# M_Board1_2011.net
KiCad netlist of a schematic drawn in Altium Designer
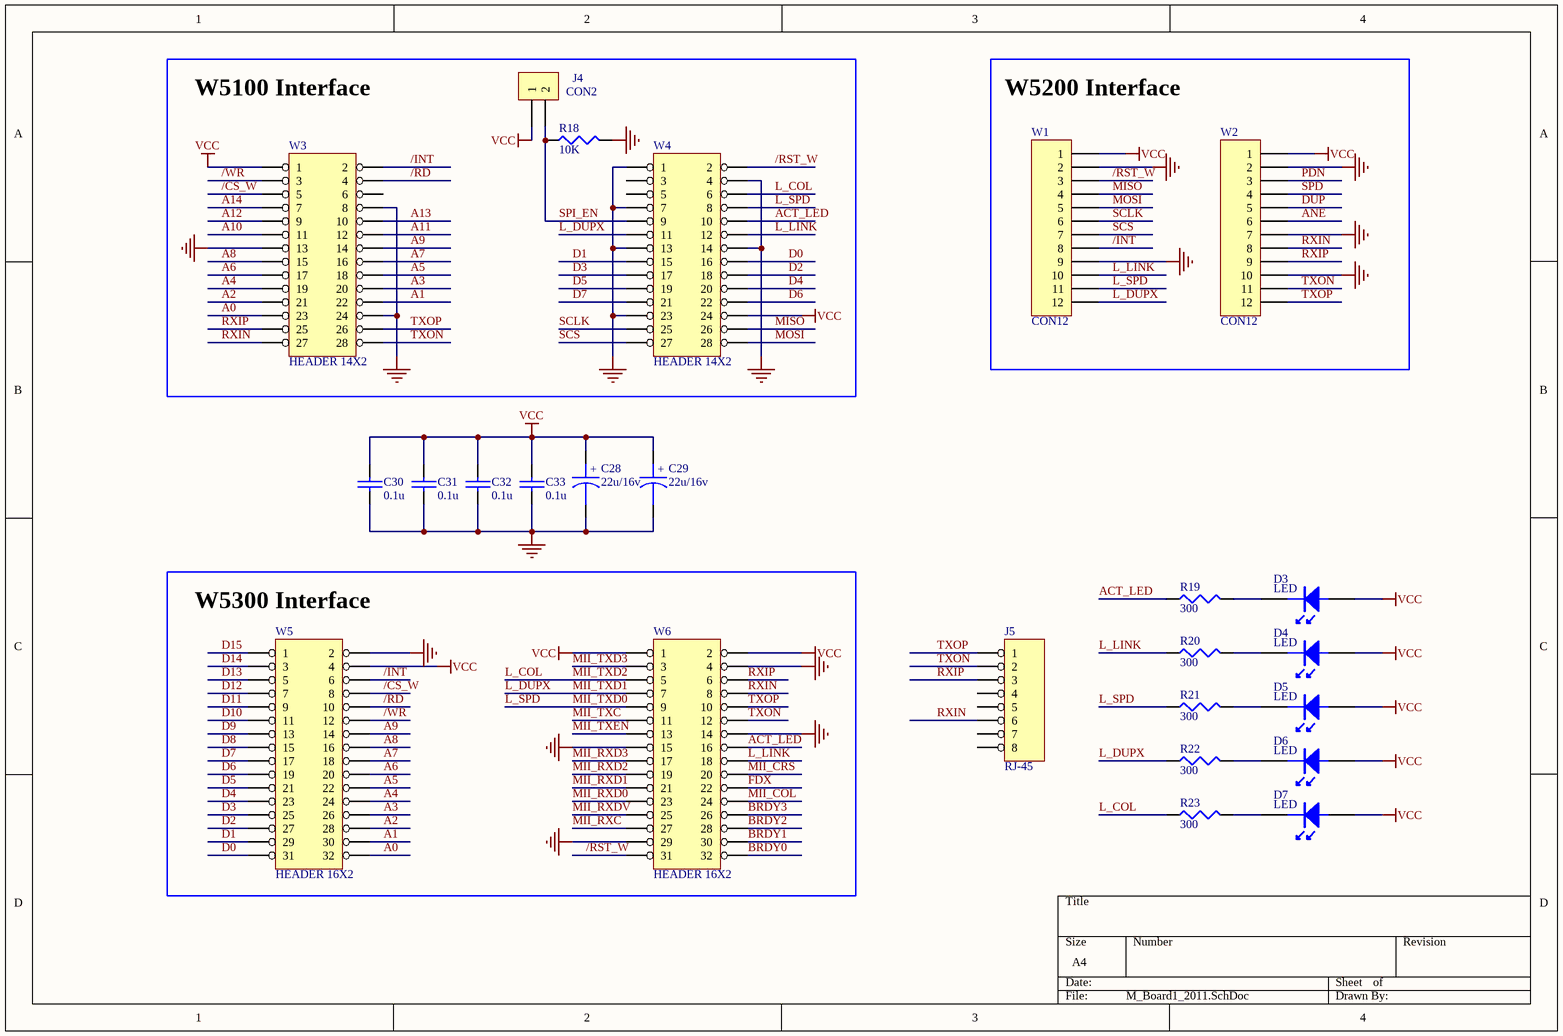
[diagram p0: M_Board1_2011.SchDoc]

(export (version "E")
  (design (tool "Eeschema 10.0.6"))
  (components
    (comp (ref "C28")
      (value "22u/16v")
      (footprint "RB.1/.2N")
      (description "Capacitor")
      (libsource (lib "*") (part "CAPACITOR POL"))
    )
    (comp (ref "C29")
      (value "22u/16v")
      (footprint "RB.1/.2N")
      (description "Capacitor")
      (libsource (lib "*") (part "CAPACITOR POL"))
    )
    (comp (ref "C30")
      (value "0.1u")
      (footprint "0603")
      (description "Capacitor")
      (libsource (lib "*") (part "CAP"))
    )
    (comp (ref "C31")
      (value "0.1u")
      (footprint "0603")
      (description "Capacitor")
      (libsource (lib "*") (part "CAP"))
    )
    (comp (ref "C32")
      (value "0.1u")
      (footprint "0603")
      (description "Capacitor")
      (libsource (lib "*") (part "CAP"))
    )
    (comp (ref "C33")
      (value "0.1u")
      (footprint "0603")
      (description "Capacitor")
      (libsource (lib "*") (part "CAP"))
    )
    (comp (ref "D3") (value "LED") (footprint "LED2P") (libsource (lib "*") (part "LED")))
    (comp (ref "D4") (value "LED") (footprint "LED2P") (libsource (lib "*") (part "LED")))
    (comp (ref "D5") (value "LED") (footprint "LED2P") (libsource (lib "*") (part "LED")))
    (comp (ref "D6") (value "LED") (footprint "LED2P") (libsource (lib "*") (part "LED")))
    (comp (ref "D7") (value "LED") (footprint "LED2P") (libsource (lib "*") (part "LED")))
    (comp (ref "J4")
      (value "CON2")
      (footprint "SIP2")
      (description "Connector")
      (libsource (lib "*") (part "CON2"))
    )
    (comp (ref "J5")
      (value "RJ-45")
      (footprint "RJ45-3")
      (description "8 Pin Header")
      (libsource (lib "*") (part "8 HEADER"))
    )
    (comp (ref "R18") (value "10K") (footprint "0603") (libsource (lib "*") (part "RES1")))
    (comp (ref "R19") (value "300") (footprint "0603") (libsource (lib "*") (part "RES1")))
    (comp (ref "R20") (value "300") (footprint "0603") (libsource (lib "*") (part "RES1")))
    (comp (ref "R21") (value "300") (footprint "0603") (libsource (lib "*") (part "RES1")))
    (comp (ref "R22") (value "300") (footprint "0603") (libsource (lib "*") (part "RES1")))
    (comp (ref "R23") (value "300") (footprint "0603") (libsource (lib "*") (part "RES1")))
    (comp (ref "W1") (value "CON12") (description "Connector") (libsource (lib "*") (part "CON12")))
    (comp (ref "W2") (value "CON12") (description "Connector") (libsource (lib "*") (part "CON12")))
    (comp (ref "W3") (value "HEADER 14X2") (footprint "IDC28-2") (libsource (lib "*") (part "HEADER 14X2")))
    (comp (ref "W4") (value "HEADER 14X2") (footprint "IDC28-2") (libsource (lib "*") (part "HEADER 14X2")))
    (comp (ref "W5") (value "HEADER 16X2") (footprint "IDC32-2") (libsource (lib "*") (part "HEADER 16X2")))
    (comp (ref "W6") (value "HEADER 16X2") (footprint "IDC32-2") (libsource (lib "*") (part "HEADER 16X2")))
  )
  (nets
    (net (code "1") (name "/A0") (class "Default")
      (node (ref "W3") (pin "23") (pinfunction "23_23") (pintype "passive"))
      (node (ref "W5") (pin "32") (pinfunction "32_32") (pintype "passive"))
    )
    (net (code "2") (name "/A1") (class "Default")
      (node (ref "W3") (pin "22") (pinfunction "22_22") (pintype "passive"))
      (node (ref "W5") (pin "30") (pinfunction "30_30") (pintype "passive"))
    )
    (net (code "3") (name "/A2") (class "Default")
      (node (ref "W3") (pin "21") (pinfunction "21_21") (pintype "passive"))
      (node (ref "W5") (pin "28") (pinfunction "28_28") (pintype "passive"))
    )
    (net (code "4") (name "/A3") (class "Default")
      (node (ref "W3") (pin "20") (pinfunction "20_20") (pintype "passive"))
      (node (ref "W5") (pin "26") (pinfunction "26_26") (pintype "passive"))
    )
    (net (code "5") (name "/A4") (class "Default")
      (node (ref "W3") (pin "19") (pinfunction "19_19") (pintype "passive"))
      (node (ref "W5") (pin "24") (pinfunction "24_24") (pintype "passive"))
    )
    (net (code "6") (name "/A5") (class "Default")
      (node (ref "W3") (pin "18") (pinfunction "18_18") (pintype "passive"))
      (node (ref "W5") (pin "22") (pinfunction "22_22") (pintype "passive"))
    )
    (net (code "7") (name "/A6") (class "Default")
      (node (ref "W3") (pin "17") (pinfunction "17_17") (pintype "passive"))
      (node (ref "W5") (pin "20") (pinfunction "20_20") (pintype "passive"))
    )
    (net (code "8") (name "/A7") (class "Default")
      (node (ref "W3") (pin "16") (pinfunction "16_16") (pintype "passive"))
      (node (ref "W5") (pin "18") (pinfunction "18_18") (pintype "passive"))
    )
    (net (code "9") (name "/A8") (class "Default")
      (node (ref "W3") (pin "15") (pinfunction "15_15") (pintype "passive"))
      (node (ref "W5") (pin "16") (pinfunction "16_16") (pintype "passive"))
    )
    (net (code "10") (name "/A9") (class "Default")
      (node (ref "W3") (pin "14") (pinfunction "14_14") (pintype "passive"))
      (node (ref "W5") (pin "14") (pinfunction "14_14") (pintype "passive"))
    )
    (net (code "11") (name "/A10") (class "Default")
      (node (ref "W3") (pin "11") (pinfunction "11_11") (pintype "passive"))
    )
    (net (code "12") (name "/A11") (class "Default")
      (node (ref "W3") (pin "12") (pinfunction "12_12") (pintype "passive"))
    )
    (net (code "13") (name "/A12") (class "Default")
      (node (ref "W3") (pin "9") (pinfunction "9_9") (pintype "passive"))
    )
    (net (code "14") (name "/A13") (class "Default")
      (node (ref "W3") (pin "10") (pinfunction "10_10") (pintype "passive"))
    )
    (net (code "15") (name "/A14") (class "Default")
      (node (ref "W3") (pin "7") (pinfunction "7_7") (pintype "passive"))
    )
    (net (code "16") (name "/ACT_LED") (class "Default")
      (node (ref "R19") (pin "1") (pinfunction "1_1") (pintype "passive"))
      (node (ref "W4") (pin "10") (pinfunction "10_10") (pintype "passive"))
      (node (ref "W6") (pin "16") (pinfunction "16_16") (pintype "passive"))
    )
    (net (code "17") (name "/ANE") (class "Default")
      (node (ref "W2") (pin "6") (pinfunction "6_6") (pintype "passive"))
    )
    (net (code "18") (name "/BRDY0") (class "Default")
      (node (ref "W6") (pin "32") (pinfunction "32_32") (pintype "passive"))
    )
    (net (code "19") (name "/BRDY1") (class "Default")
      (node (ref "W6") (pin "30") (pinfunction "30_30") (pintype "passive"))
    )
    (net (code "20") (name "/BRDY2") (class "Default")
      (node (ref "W6") (pin "28") (pinfunction "28_28") (pintype "passive"))
    )
    (net (code "21") (name "/BRDY3") (class "Default")
      (node (ref "W6") (pin "26") (pinfunction "26_26") (pintype "passive"))
    )
    (net (code "22") (name "/D0") (class "Default")
      (node (ref "W4") (pin "16") (pinfunction "16_16") (pintype "passive"))
      (node (ref "W5") (pin "31") (pinfunction "31_31") (pintype "passive"))
    )
    (net (code "23") (name "/D1") (class "Default")
      (node (ref "W4") (pin "15") (pinfunction "15_15") (pintype "passive"))
      (node (ref "W5") (pin "29") (pinfunction "29_29") (pintype "passive"))
    )
    (net (code "24") (name "/D2") (class "Default")
      (node (ref "W4") (pin "18") (pinfunction "18_18") (pintype "passive"))
      (node (ref "W5") (pin "27") (pinfunction "27_27") (pintype "passive"))
    )
    (net (code "25") (name "/D3") (class "Default")
      (node (ref "W4") (pin "17") (pinfunction "17_17") (pintype "passive"))
      (node (ref "W5") (pin "25") (pinfunction "25_25") (pintype "passive"))
    )
    (net (code "26") (name "/D4") (class "Default")
      (node (ref "W4") (pin "20") (pinfunction "20_20") (pintype "passive"))
      (node (ref "W5") (pin "23") (pinfunction "23_23") (pintype "passive"))
    )
    (net (code "27") (name "/D5") (class "Default")
      (node (ref "W4") (pin "19") (pinfunction "19_19") (pintype "passive"))
      (node (ref "W5") (pin "21") (pinfunction "21_21") (pintype "passive"))
    )
    (net (code "28") (name "/D6") (class "Default")
      (node (ref "W4") (pin "22") (pinfunction "22_22") (pintype "passive"))
      (node (ref "W5") (pin "19") (pinfunction "19_19") (pintype "passive"))
    )
    (net (code "29") (name "/D7") (class "Default")
      (node (ref "W4") (pin "21") (pinfunction "21_21") (pintype "passive"))
      (node (ref "W5") (pin "17") (pinfunction "17_17") (pintype "passive"))
    )
    (net (code "30") (name "/D8") (class "Default")
      (node (ref "W5") (pin "15") (pinfunction "15_15") (pintype "passive"))
    )
    (net (code "31") (name "/D9") (class "Default")
      (node (ref "W5") (pin "13") (pinfunction "13_13") (pintype "passive"))
    )
    (net (code "32") (name "/D10") (class "Default")
      (node (ref "W5") (pin "11") (pinfunction "11_11") (pintype "passive"))
    )
    (net (code "33") (name "/D11") (class "Default")
      (node (ref "W5") (pin "9") (pinfunction "9_9") (pintype "passive"))
    )
    (net (code "34") (name "/D12") (class "Default")
      (node (ref "W5") (pin "7") (pinfunction "7_7") (pintype "passive"))
    )
    (net (code "35") (name "/D13") (class "Default")
      (node (ref "W5") (pin "5") (pinfunction "5_5") (pintype "passive"))
    )
    (net (code "36") (name "/D14") (class "Default")
      (node (ref "W5") (pin "3") (pinfunction "3_3") (pintype "passive"))
    )
    (net (code "37") (name "/D15") (class "Default")
      (node (ref "W5") (pin "1") (pinfunction "1_1") (pintype "passive"))
    )
    (net (code "38") (name "/DUP") (class "Default")
      (node (ref "W2") (pin "5") (pinfunction "5_5") (pintype "passive"))
    )
    (net (code "39") (name "/FDX") (class "Default")
      (node (ref "W6") (pin "22") (pinfunction "22_22") (pintype "passive"))
    )
    (net (code "40") (name "/L_COL") (class "Default")
      (node (ref "R23") (pin "1") (pinfunction "1_1") (pintype "passive"))
      (node (ref "W4") (pin "6") (pinfunction "6_6") (pintype "passive"))
      (node (ref "W6") (pin "5") (pinfunction "5_5") (pintype "passive"))
    )
    (net (code "41") (name "/L_DUPX") (class "Default")
      (node (ref "R22") (pin "1") (pinfunction "1_1") (pintype "passive"))
      (node (ref "W1") (pin "12") (pinfunction "12_12") (pintype "passive"))
      (node (ref "W4") (pin "11") (pinfunction "11_11") (pintype "passive"))
      (node (ref "W6") (pin "7") (pinfunction "7_7") (pintype "passive"))
    )
    (net (code "42") (name "/L_LINK") (class "Default")
      (node (ref "R20") (pin "1") (pinfunction "1_1") (pintype "passive"))
      (node (ref "W1") (pin "10") (pinfunction "10_10") (pintype "passive"))
      (node (ref "W4") (pin "12") (pinfunction "12_12") (pintype "passive"))
      (node (ref "W6") (pin "18") (pinfunction "18_18") (pintype "passive"))
    )
    (net (code "43") (name "/L_SPD") (class "Default")
      (node (ref "R21") (pin "1") (pinfunction "1_1") (pintype "passive"))
      (node (ref "W1") (pin "11") (pinfunction "11_11") (pintype "passive"))
      (node (ref "W4") (pin "8") (pinfunction "8_8") (pintype "passive"))
      (node (ref "W6") (pin "9") (pinfunction "9_9") (pintype "passive"))
    )
    (net (code "44") (name "/MII_COL") (class "Default")
      (node (ref "W6") (pin "24") (pinfunction "24_24") (pintype "passive"))
    )
    (net (code "45") (name "/MII_CRS") (class "Default")
      (node (ref "W6") (pin "20") (pinfunction "20_20") (pintype "passive"))
    )
    (net (code "46") (name "/MII_RXC") (class "Default")
      (node (ref "W6") (pin "27") (pinfunction "27_27") (pintype "passive"))
    )
    (net (code "47") (name "/MII_RXD0") (class "Default")
      (node (ref "W6") (pin "23") (pinfunction "23_23") (pintype "passive"))
    )
    (net (code "48") (name "/MII_RXD1") (class "Default")
      (node (ref "W6") (pin "21") (pinfunction "21_21") (pintype "passive"))
    )
    (net (code "49") (name "/MII_RXD2") (class "Default")
      (node (ref "W6") (pin "19") (pinfunction "19_19") (pintype "passive"))
    )
    (net (code "50") (name "/MII_RXD3") (class "Default")
      (node (ref "W6") (pin "17") (pinfunction "17_17") (pintype "passive"))
    )
    (net (code "51") (name "/MII_RXDV") (class "Default")
      (node (ref "W6") (pin "25") (pinfunction "25_25") (pintype "passive"))
    )
    (net (code "52") (name "/MII_TXC") (class "Default")
      (node (ref "W6") (pin "11") (pinfunction "11_11") (pintype "passive"))
    )
    (net (code "53") (name "/MII_TXD3") (class "Default")
      (node (ref "W6") (pin "3") (pinfunction "3_3") (pintype "passive"))
    )
    (net (code "54") (name "/MII_TXEN") (class "Default")
      (node (ref "W6") (pin "13") (pinfunction "13_13") (pintype "passive"))
    )
    (net (code "55") (name "/MISO") (class "Default")
      (node (ref "W1") (pin "4") (pinfunction "4_4") (pintype "passive"))
      (node (ref "W4") (pin "26") (pinfunction "26_26") (pintype "passive"))
    )
    (net (code "56") (name "/MOSI") (class "Default")
      (node (ref "W1") (pin "5") (pinfunction "5_5") (pintype "passive"))
      (node (ref "W4") (pin "28") (pinfunction "28_28") (pintype "passive"))
    )
    (net (code "57") (name "/PDN") (class "Default")
      (node (ref "W2") (pin "3") (pinfunction "3_3") (pintype "passive"))
    )
    (net (code "58") (name "/RXIN") (class "Default")
      (node (ref "J5") (pin "6") (pinfunction "6_6") (pintype "passive"))
      (node (ref "W2") (pin "8") (pinfunction "8_8") (pintype "passive"))
      (node (ref "W3") (pin "27") (pinfunction "27_27") (pintype "passive"))
      (node (ref "W6") (pin "8") (pinfunction "8_8") (pintype "passive"))
    )
    (net (code "59") (name "/RXIP") (class "Default")
      (node (ref "J5") (pin "3") (pinfunction "3_3") (pintype "passive"))
      (node (ref "W2") (pin "9") (pinfunction "9_9") (pintype "passive"))
      (node (ref "W3") (pin "25") (pinfunction "25_25") (pintype "passive"))
      (node (ref "W6") (pin "6") (pinfunction "6_6") (pintype "passive"))
    )
    (net (code "60") (name "/SCLK") (class "Default")
      (node (ref "W1") (pin "6") (pinfunction "6_6") (pintype "passive"))
      (node (ref "W4") (pin "25") (pinfunction "25_25") (pintype "passive"))
    )
    (net (code "61") (name "/SCS") (class "Default")
      (node (ref "W1") (pin "7") (pinfunction "7_7") (pintype "passive"))
      (node (ref "W4") (pin "27") (pinfunction "27_27") (pintype "passive"))
    )
    (net (code "62") (name "/SPD") (class "Default")
      (node (ref "W2") (pin "4") (pinfunction "4_4") (pintype "passive"))
    )
    (net (code "63") (name "/SPI_EN") (class "Default")
      (node (ref "J4") (pin "2") (pinfunction "2_2") (pintype "passive"))
      (node (ref "R18") (pin "1") (pinfunction "1_1") (pintype "passive"))
      (node (ref "W4") (pin "9") (pinfunction "9_9") (pintype "passive"))
    )
    (net (code "64") (name "/TXON") (class "Default")
      (node (ref "J5") (pin "2") (pinfunction "2_2") (pintype "passive"))
      (node (ref "W2") (pin "11") (pinfunction "11_11") (pintype "passive"))
      (node (ref "W3") (pin "28") (pinfunction "28_28") (pintype "passive"))
      (node (ref "W6") (pin "12") (pinfunction "12_12") (pintype "passive"))
    )
    (net (code "65") (name "/TXOP") (class "Default")
      (node (ref "J5") (pin "1") (pinfunction "1_1") (pintype "passive"))
      (node (ref "W2") (pin "12") (pinfunction "12_12") (pintype "passive"))
      (node (ref "W3") (pin "26") (pinfunction "26_26") (pintype "passive"))
      (node (ref "W6") (pin "10") (pinfunction "10_10") (pintype "passive"))
    )
    (net (code "66") (name "/{slash}CS_W") (class "Default")
      (node (ref "W3") (pin "5") (pinfunction "5_5") (pintype "passive"))
      (node (ref "W5") (pin "8") (pinfunction "8_8") (pintype "passive"))
    )
    (net (code "67") (name "/{slash}INT") (class "Default")
      (node (ref "W1") (pin "8") (pinfunction "8_8") (pintype "passive"))
      (node (ref "W3") (pin "2") (pinfunction "2_2") (pintype "passive"))
      (node (ref "W5") (pin "6") (pinfunction "6_6") (pintype "passive"))
    )
    (net (code "68") (name "/{slash}RD") (class "Default")
      (node (ref "W3") (pin "4") (pinfunction "4_4") (pintype "passive"))
      (node (ref "W5") (pin "10") (pinfunction "10_10") (pintype "passive"))
    )
    (net (code "69") (name "/{slash}RST_W") (class "Default")
      (node (ref "W1") (pin "3") (pinfunction "3_3") (pintype "passive"))
      (node (ref "W4") (pin "2") (pinfunction "2_2") (pintype "passive"))
      (node (ref "W6") (pin "31") (pinfunction "31_31") (pintype "passive"))
    )
    (net (code "70") (name "/{slash}WR") (class "Default")
      (node (ref "W3") (pin "3") (pinfunction "3_3") (pintype "passive"))
      (node (ref "W5") (pin "12") (pinfunction "12_12") (pintype "passive"))
    )
    (net (code "71") (name "GND") (class "Default")
      (node (ref "C28") (pin "2") (pinfunction "2_2") (pintype "passive"))
      (node (ref "C29") (pin "2") (pinfunction "2_2") (pintype "passive"))
      (node (ref "C30") (pin "1") (pinfunction "1_1") (pintype "passive"))
      (node (ref "C31") (pin "1") (pinfunction "1_1") (pintype "passive"))
      (node (ref "C32") (pin "1") (pinfunction "1_1") (pintype "passive"))
      (node (ref "C33") (pin "1") (pinfunction "1_1") (pintype "passive"))
      (node (ref "R18") (pin "2") (pinfunction "2_2") (pintype "passive"))
      (node (ref "W1") (pin "2") (pinfunction "2_2") (pintype "passive"))
      (node (ref "W1") (pin "9") (pinfunction "9_9") (pintype "passive"))
      (node (ref "W2") (pin "10") (pinfunction "10_10") (pintype "passive"))
      (node (ref "W2") (pin "2") (pinfunction "2_2") (pintype "passive"))
      (node (ref "W2") (pin "7") (pinfunction "7_7") (pintype "passive"))
      (node (ref "W3") (pin "13") (pinfunction "13_13") (pintype "passive"))
      (node (ref "W3") (pin "24") (pinfunction "24_24") (pintype "passive"))
      (node (ref "W3") (pin "8") (pinfunction "8_8") (pintype "passive"))
      (node (ref "W4") (pin "1") (pinfunction "1_1") (pintype "passive"))
      (node (ref "W4") (pin "13") (pinfunction "13_13") (pintype "passive"))
      (node (ref "W4") (pin "14") (pinfunction "14_14") (pintype "passive"))
      (node (ref "W4") (pin "23") (pinfunction "23_23") (pintype "passive"))
      (node (ref "W4") (pin "4") (pinfunction "4_4") (pintype "passive"))
      (node (ref "W4") (pin "7") (pinfunction "7_7") (pintype "passive"))
      (node (ref "W5") (pin "2") (pinfunction "2_2") (pintype "passive"))
      (node (ref "W6") (pin "14") (pinfunction "14_14") (pintype "passive"))
      (node (ref "W6") (pin "15") (pinfunction "15_15") (pintype "passive"))
      (node (ref "W6") (pin "29") (pinfunction "29_29") (pintype "passive"))
      (node (ref "W6") (pin "4") (pinfunction "4_4") (pintype "passive"))
    )
    (net (code "72") (name "Net-(D3-2)") (class "Default")
      (node (ref "D3") (pin "K") (pinfunction "2_K") (pintype "passive"))
      (node (ref "R19") (pin "2") (pinfunction "2_2") (pintype "passive"))
    )
    (net (code "73") (name "Net-(D4-2)") (class "Default")
      (node (ref "D4") (pin "K") (pinfunction "2_K") (pintype "passive"))
      (node (ref "R20") (pin "2") (pinfunction "2_2") (pintype "passive"))
    )
    (net (code "74") (name "Net-(D5-2)") (class "Default")
      (node (ref "D5") (pin "K") (pinfunction "2_K") (pintype "passive"))
      (node (ref "R21") (pin "2") (pinfunction "2_2") (pintype "passive"))
    )
    (net (code "75") (name "Net-(D6-2)") (class "Default")
      (node (ref "D6") (pin "K") (pinfunction "2_K") (pintype "passive"))
      (node (ref "R22") (pin "2") (pinfunction "2_2") (pintype "passive"))
    )
    (net (code "76") (name "Net-(D7-2)") (class "Default")
      (node (ref "D7") (pin "K") (pinfunction "2_K") (pintype "passive"))
      (node (ref "R23") (pin "2") (pinfunction "2_2") (pintype "passive"))
    )
    (net (code "77") (name "VCC") (class "Default")
      (node (ref "C28") (pin "1") (pinfunction "1_1") (pintype "passive"))
      (node (ref "C29") (pin "1") (pinfunction "1_1") (pintype "passive"))
      (node (ref "C30") (pin "2") (pinfunction "2_2") (pintype "passive"))
      (node (ref "C31") (pin "2") (pinfunction "2_2") (pintype "passive"))
      (node (ref "C32") (pin "2") (pinfunction "2_2") (pintype "passive"))
      (node (ref "C33") (pin "2") (pinfunction "2_2") (pintype "passive"))
      (node (ref "D3") (pin "A") (pinfunction "1_A") (pintype "passive"))
      (node (ref "D4") (pin "A") (pinfunction "1_A") (pintype "passive"))
      (node (ref "D5") (pin "A") (pinfunction "1_A") (pintype "passive"))
      (node (ref "D6") (pin "A") (pinfunction "1_A") (pintype "passive"))
      (node (ref "D7") (pin "A") (pinfunction "1_A") (pintype "passive"))
      (node (ref "J4") (pin "1") (pinfunction "1_1") (pintype "passive"))
      (node (ref "W1") (pin "1") (pinfunction "1_1") (pintype "passive"))
      (node (ref "W2") (pin "1") (pinfunction "1_1") (pintype "passive"))
      (node (ref "W3") (pin "1") (pinfunction "1_1") (pintype "passive"))
      (node (ref "W4") (pin "24") (pinfunction "24_24") (pintype "passive"))
      (node (ref "W5") (pin "4") (pinfunction "4_4") (pintype "passive"))
      (node (ref "W6") (pin "1") (pinfunction "1_1") (pintype "passive"))
      (node (ref "W6") (pin "2") (pinfunction "2_2") (pintype "passive"))
    )
    (net (code "78") (name "unconnected-(J5-Pad4)") (class "Default")
      (node (ref "J5") (pin "4") (pinfunction "4_4") (pintype "passive"))
    )
    (net (code "79") (name "unconnected-(J5-Pad5)") (class "Default")
      (node (ref "J5") (pin "5") (pinfunction "5_5") (pintype "passive"))
    )
    (net (code "80") (name "unconnected-(J5-Pad7)") (class "Default")
      (node (ref "J5") (pin "7") (pinfunction "7_7") (pintype "passive"))
    )
    (net (code "81") (name "unconnected-(J5-Pad8)") (class "Default")
      (node (ref "J5") (pin "8") (pinfunction "8_8") (pintype "passive"))
    )
    (net (code "82") (name "unconnected-(W3-Pad6)") (class "Default")
      (node (ref "W3") (pin "6") (pinfunction "6_6") (pintype "passive"))
    )
    (net (code "83") (name "unconnected-(W4-Pad3)") (class "Default")
      (node (ref "W4") (pin "3") (pinfunction "3_3") (pintype "passive"))
    )
    (net (code "84") (name "unconnected-(W4-Pad5)") (class "Default")
      (node (ref "W4") (pin "5") (pinfunction "5_5") (pintype "passive"))
    )
  )
)
